# AuxHalfH.net
KiCad netlist of a schematic drawn in Altium Designer
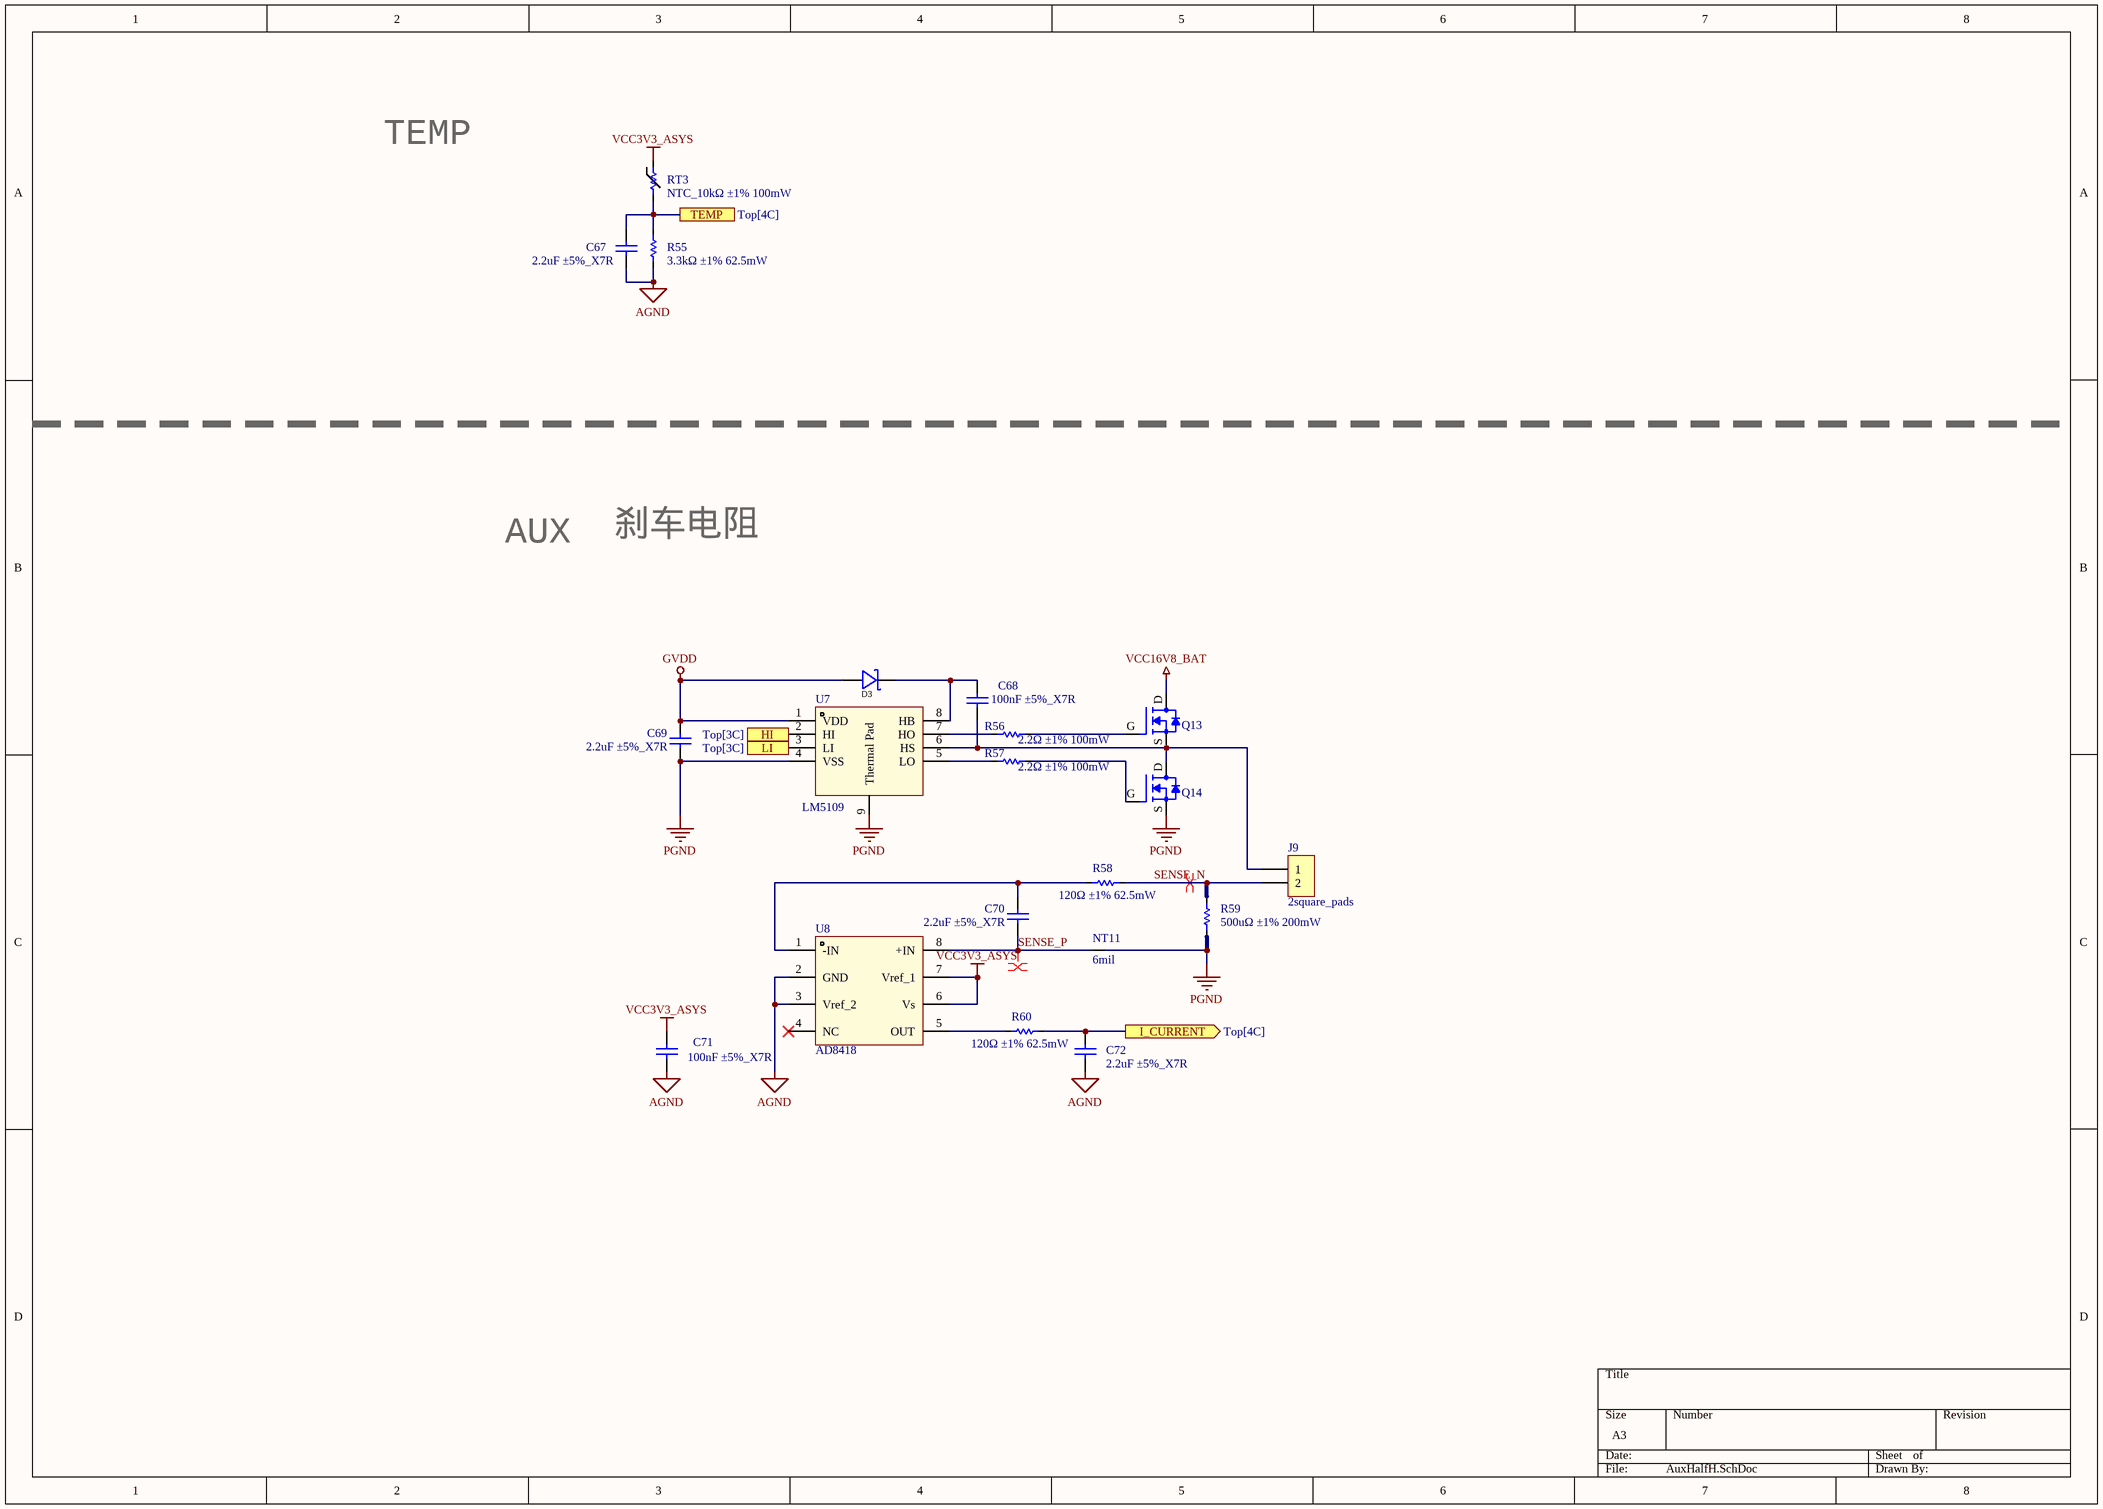
[diagram p0: AuxHalfH.SchDoc]

(export (version "E")
  (design (tool "Eeschema 10.0.6"))
  (components
    (comp (ref "C67")
      (value "2.2uF ±5%_X7R")
      (footprint "WCAP-CSGP_0402_L1W0.5H0.5")
      (description "Capacitor")
      (fields (field (name "PUBLISHER") "Altium Limited"))
      (libsource (lib "Component") (part "Cap"))
    )
    (comp (ref "C68")
      (value "100nF ±5%_X7R")
      (footprint "WCAP-CSGP_0603_L1.6W0.8H0.8_Reflow")
      (description "Capacitor")
      (fields (field (name "PUBLISHER") "Altium Limited"))
      (libsource (lib "Component") (part "Cap"))
    )
    (comp (ref "C69")
      (value "2.2uF ±5%_X7R")
      (footprint "WCAP-CSGP_0603_L1.6W0.8H0.8_Reflow")
      (description "Capacitor")
      (fields (field (name "PUBLISHER") "Altium Limited"))
      (libsource (lib "Component") (part "Cap"))
    )
    (comp (ref "C70")
      (value "2.2uF ±5%_X7R")
      (footprint "WCAP-CSGP_0402_L1W0.5H0.5")
      (description "Capacitor")
      (fields (field (name "PUBLISHER") "Altium Limited"))
      (libsource (lib "Component") (part "Cap"))
    )
    (comp (ref "C71")
      (value "100nF ±5%_X7R")
      (footprint "WCAP-CSGP_0402_L1W0.5H0.5")
      (description "Capacitor")
      (fields (field (name "PUBLISHER") "Altium Limited"))
      (libsource (lib "Component") (part "Cap"))
    )
    (comp (ref "C72")
      (value "2.2uF ±5%_X7R")
      (footprint "WCAP-CSGP_0402_L1W0.5H0.5")
      (description "Capacitor")
      (fields (field (name "PUBLISHER") "Altium Limited"))
      (libsource (lib "Component") (part "Cap"))
    )
    (comp (ref "D3")
      (value "B340A-13-F")
      (footprint "SMA_L4.4-W2.6-LS5.0-RD")
      (description "直流反向耐压(Vr):40V;平均整流电流(Io):3A;正向压降(Vf):500mV@3A;")
      (fields (field (name "MANUFACTURER") "DIODES(美台)"))
      (libsource (lib "Component") (part "Diode_Schottky"))
    )
    (comp (ref "J9")
      (value "2square_pads")
      (footprint "2pads_square")
      (libsource (lib "Connectivity_Plugs") (part "2square_pads"))
    )
    (comp (ref "NT11") (value "6mil") (footprint "NETTIE_6mil") (libsource (lib "Component") (part "NETTIE")))
    (comp (ref "Q13")
      (value "BSC027N04LSG")
      (footprint "NRVTS10100EMFST1G")
      (description "MOSFET – Power, Single,\r\nN-Channel, PG-TDSON-8\r\nSuperSO8 5x6\r\n40 V, 139 A")
      (fields
        (field (name "MANUFACTURER") "ON Semiconductor")
        (field (name "MANUFACTURER PART NUMBER") "NTMFS4935NT1G")
      )
      (libsource (lib "Component") (part "MOSFET-N"))
    )
    (comp (ref "Q14")
      (value "BSC027N04LSG")
      (footprint "NRVTS10100EMFST1G")
      (description "MOSFET – Power, Single,\r\nN-Channel, PG-TDSON-8\r\nSuperSO8 5x6\r\n40 V, 139 A")
      (fields
        (field (name "MANUFACTURER") "ON Semiconductor")
        (field (name "MANUFACTURER PART NUMBER") "NTMFS4935NT1G")
      )
      (libsource (lib "Component") (part "MOSFET-N"))
    )
    (comp (ref "R55")
      (value "3.3kΩ ±1% 62.5mW")
      (footprint "WRIS-KSKE_0402")
      (description "Resistor")
      (fields (field (name "PUBLISHER") "Altium Limited"))
      (libsource (lib "Component") (part "Res"))
    )
    (comp (ref "R56")
      (value "2.2Ω ±1% 100mW")
      (footprint "WRIS-KSKE_0402")
      (description "Resistor")
      (fields (field (name "PUBLISHER") "Altium Limited"))
      (libsource (lib "Component") (part "Res"))
    )
    (comp (ref "R57")
      (value "2.2Ω ±1% 100mW")
      (footprint "WRIS-KSKE_0402")
      (description "Resistor")
      (fields (field (name "PUBLISHER") "Altium Limited"))
      (libsource (lib "Component") (part "Res"))
    )
    (comp (ref "R58")
      (value "120Ω ±1% 62.5mW")
      (footprint "WRIS-KSKE_0402")
      (description "Resistor")
      (fields (field (name "PUBLISHER") "Altium Limited"))
      (libsource (lib "Component") (part "Res"))
    )
    (comp (ref "R59")
      (value "500uΩ ±1% 200mW")
      (footprint "WRIS-KSKE_2512")
      (description "Resistor")
      (fields (field (name "PUBLISHER") "Altium Limited"))
      (libsource (lib "Component") (part "Res"))
    )
    (comp (ref "R60")
      (value "120Ω ±1% 62.5mW")
      (footprint "WRIS-KSKE_0402")
      (description "Resistor")
      (fields (field (name "PUBLISHER") "Altium Limited"))
      (libsource (lib "Component") (part "Res"))
    )
    (comp (ref "RT3")
      (value "NTC_10kΩ ±1% 100mW")
      (footprint "WRIS-KSKE_0402")
      (description "THERMISTOR 10K OHM NTC 0402 SMD")
      (libsource (lib "Component") (part "TEMP RES"))
    )
    (comp (ref "U7")
      (value "LM5109")
      (footprint "SON80P400X80_HS-9N")
      (description "DRIVER, MOSFET, HALF BRIDGE, WSON-8, 1A")
      (libsource (lib "IC") (part "LM5109"))
    )
    (comp (ref "U8")
      (value "AD8418")
      (footprint "MSOP-8_L3.0-W3.0-P0.65-LS5.0-BL")
      (description "ANALOG DEVICES Current Sense Amplifier, Bidirectional, 1, 130 µA, NSOIC")
      (libsource (lib "IC") (part "AD8418WBRZ"))
    )
  )
  (nets
    (net (code "1") (name "/HI") (class "Default")
      (node (ref "U7") (pin "2") (pinfunction "HI_2") (pintype "passive"))
    )
    (net (code "2") (name "/I_CURRENT") (class "Default")
      (node (ref "C72") (pin "2") (pinfunction "2_2") (pintype "passive"))
      (node (ref "R60") (pin "1") (pinfunction "1_1") (pintype "passive"))
    )
    (net (code "3") (name "/LI") (class "Default")
      (node (ref "U7") (pin "3") (pinfunction "LI_3") (pintype "passive"))
    )
    (net (code "4") (name "/SENSE_N") (class "Default")
      (node (ref "J9") (pin "2") (pinfunction "2_2") (pintype "passive"))
      (node (ref "R58") (pin "1") (pinfunction "1_1") (pintype "passive"))
      (node (ref "R59") (pin "1") (pinfunction "1_1") (pintype "passive"))
    )
    (net (code "5") (name "/SENSE_P") (class "Default")
      (node (ref "C70") (pin "1") (pinfunction "1_1") (pintype "passive"))
      (node (ref "NT11") (pin "2") (pinfunction "2_2") (pintype "passive"))
      (node (ref "U8") (pin "8") (pinfunction "+IN_8") (pintype "passive"))
    )
    (net (code "6") (name "/TEMP") (class "Default")
      (node (ref "C67") (pin "2") (pinfunction "2_2") (pintype "passive"))
      (node (ref "R55") (pin "2") (pinfunction "2_2") (pintype "passive"))
      (node (ref "RT3") (pin "2") (pinfunction "2_2") (pintype "passive"))
    )
    (net (code "7") (name "AGND") (class "Default")
      (node (ref "C67") (pin "1") (pinfunction "1_1") (pintype "passive"))
      (node (ref "C71") (pin "1") (pinfunction "1_1") (pintype "passive"))
      (node (ref "C72") (pin "1") (pinfunction "1_1") (pintype "passive"))
      (node (ref "R55") (pin "1") (pinfunction "1_1") (pintype "passive"))
      (node (ref "U8") (pin "2") (pinfunction "GND_2") (pintype "passive"))
      (node (ref "U8") (pin "3") (pinfunction "Vref_2_3") (pintype "passive"))
    )
    (net (code "8") (name "GVDD") (class "Default")
      (node (ref "C69") (pin "2") (pinfunction "2_2") (pintype "passive"))
      (node (ref "D3") (pin "2") (pinfunction "A_2") (pintype "passive"))
      (node (ref "U7") (pin "1") (pinfunction "VDD_1") (pintype "passive"))
    )
    (net (code "9") (name "Net-(D3-K)") (class "Default")
      (node (ref "C68") (pin "2") (pinfunction "2_2") (pintype "passive"))
      (node (ref "D3") (pin "1") (pinfunction "K_1") (pintype "passive"))
      (node (ref "U7") (pin "8") (pinfunction "HB_8") (pintype "passive"))
    )
    (net (code "10") (name "Net-(Q13-PadG)") (class "Default")
      (node (ref "Q13") (pin "G") (pinfunction "G_G") (pintype "passive"))
      (node (ref "R56") (pin "1") (pinfunction "1_1") (pintype "passive"))
    )
    (net (code "11") (name "Net-(Q14-PadG)") (class "Default")
      (node (ref "Q14") (pin "G") (pinfunction "G_G") (pintype "passive"))
      (node (ref "R57") (pin "1") (pinfunction "1_1") (pintype "passive"))
    )
    (net (code "12") (name "Net-(U7-HO)") (class "Default")
      (node (ref "R56") (pin "2") (pinfunction "2_2") (pintype "passive"))
      (node (ref "U7") (pin "7") (pinfunction "HO_7") (pintype "passive"))
    )
    (net (code "13") (name "Net-(U7-HS)") (class "Default")
      (node (ref "C68") (pin "1") (pinfunction "1_1") (pintype "passive"))
      (node (ref "J9") (pin "1") (pinfunction "1_1") (pintype "passive"))
      (node (ref "Q13") (pin "S") (pinfunction "S_S") (pintype "passive"))
      (node (ref "Q14") (pin "D") (pinfunction "D_D") (pintype "passive"))
      (node (ref "U7") (pin "6") (pinfunction "HS_6") (pintype "passive"))
    )
    (net (code "14") (name "Net-(U7-LO)") (class "Default")
      (node (ref "R57") (pin "2") (pinfunction "2_2") (pintype "passive"))
      (node (ref "U7") (pin "5") (pinfunction "LO_5") (pintype "passive"))
    )
    (net (code "15") (name "Net-(U8--IN)") (class "Default")
      (node (ref "C70") (pin "2") (pinfunction "2_2") (pintype "passive"))
      (node (ref "R58") (pin "2") (pinfunction "2_2") (pintype "passive"))
      (node (ref "U8") (pin "1") (pinfunction "-IN_1") (pintype "passive"))
    )
    (net (code "16") (name "Net-(U8-OUT)") (class "Default")
      (node (ref "R60") (pin "2") (pinfunction "2_2") (pintype "passive"))
      (node (ref "U8") (pin "5") (pinfunction "OUT_5") (pintype "passive"))
    )
    (net (code "17") (name "PGND") (class "Default")
      (node (ref "C69") (pin "1") (pinfunction "1_1") (pintype "passive"))
      (node (ref "NT11") (pin "1") (pinfunction "1_1") (pintype "passive"))
      (node (ref "Q14") (pin "S") (pinfunction "S_S") (pintype "passive"))
      (node (ref "R59") (pin "2") (pinfunction "2_2") (pintype "passive"))
      (node (ref "U7") (pin "4") (pinfunction "VSS_4") (pintype "passive"))
      (node (ref "U7") (pin "9") (pinfunction "Thermal_Pad_9") (pintype "passive"))
    )
    (net (code "18") (name "VCC3V3_ASYS") (class "Default")
      (node (ref "C71") (pin "2") (pinfunction "2_2") (pintype "passive"))
      (node (ref "RT3") (pin "1") (pinfunction "1_1") (pintype "passive"))
      (node (ref "U8") (pin "6") (pinfunction "Vs_6") (pintype "passive"))
      (node (ref "U8") (pin "7") (pinfunction "Vref_1_7") (pintype "passive"))
    )
    (net (code "19") (name "VCC16V8_BAT") (class "Default")
      (node (ref "Q13") (pin "D") (pinfunction "D_D") (pintype "passive"))
    )
    (net (code "20") (name "unconnected-(U8-NC-Pad4)") (class "Default")
      (node (ref "U8") (pin "4") (pinfunction "NC_4") (pintype "passive+no_connect"))
    )
  )
)
